# log.net
KiCad netlist of a schematic drawn in EAGLE
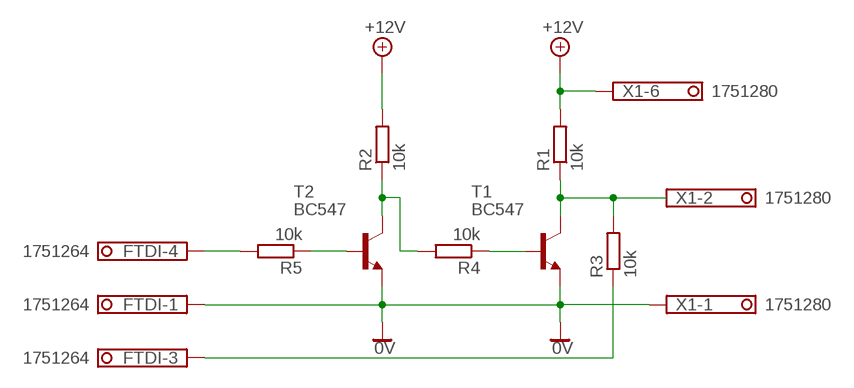
[diagram p0: schematic, sheet 1]

(export (version "E")
  (design (tool "Eeschema 10.0.6"))
  (components
    (comp (ref "FTDI")
      (value "1751264")
      (footprint "eagle-import:1751264")
      (libsource (lib "eagle-import") (part "1751264"))
    )
    (comp (ref "R1")
      (value "10k")
      (footprint "eagle-import:0204_5")
      (libsource (lib "eagle-import") (part "R-EU_0204/5"))
    )
    (comp (ref "R2")
      (value "10k")
      (footprint "eagle-import:0204_5")
      (libsource (lib "eagle-import") (part "R-EU_0204/5"))
    )
    (comp (ref "R3")
      (value "10k")
      (footprint "eagle-import:0204_5")
      (libsource (lib "eagle-import") (part "R-EU_0204/5"))
    )
    (comp (ref "R4")
      (value "10k")
      (footprint "eagle-import:0204_5")
      (libsource (lib "eagle-import") (part "R-EU_0204/5"))
    )
    (comp (ref "R5")
      (value "10k")
      (footprint "eagle-import:0204_5")
      (libsource (lib "eagle-import") (part "R-EU_0204/5"))
    )
    (comp (ref "T1")
      (value "BC547")
      (footprint "eagle-import:TO92")
      (libsource (lib "eagle-import") (part "BC547"))
    )
    (comp (ref "T2")
      (value "BC547")
      (footprint "eagle-import:TO92")
      (libsource (lib "eagle-import") (part "BC547"))
    )
    (comp (ref "X1")
      (value "1751280")
      (footprint "eagle-import:1751280")
      (libsource (lib "eagle-import") (part "1751280"))
    )
  )
  (nets
    (net (code "1") (name "+12V") (class "Default")
      (node (ref "R1") (pin "2") (pinfunction "2_2") (pintype "passive"))
      (node (ref "R2") (pin "2") (pinfunction "2_2") (pintype "passive"))
      (node (ref "X1") (pin "6") (pinfunction "K_6") (pintype "passive"))
    )
    (net (code "2") (name "0V") (class "Default")
      (node (ref "FTDI") (pin "1") (pinfunction "K_1") (pintype "passive"))
      (node (ref "T1") (pin "1") (pinfunction "E_1") (pintype "passive"))
      (node (ref "T2") (pin "1") (pinfunction "E_1") (pintype "passive"))
      (node (ref "X1") (pin "1") (pinfunction "K_1") (pintype "passive"))
    )
    (net (code "3") (name "Net-(FTDIC-K)") (class "Default")
      (node (ref "FTDI") (pin "3") (pinfunction "K_3") (pintype "passive"))
      (node (ref "R3") (pin "1") (pinfunction "1_1") (pintype "passive"))
    )
    (net (code "4") (name "Net-(FTDID-K)") (class "Default")
      (node (ref "FTDI") (pin "4") (pinfunction "K_4") (pintype "passive"))
      (node (ref "R5") (pin "2") (pinfunction "2_2") (pintype "passive"))
    )
    (net (code "5") (name "Net-(T1-B)") (class "Default")
      (node (ref "R4") (pin "1") (pinfunction "1_1") (pintype "passive"))
      (node (ref "T1") (pin "2") (pinfunction "B_2") (pintype "passive"))
    )
    (net (code "6") (name "Net-(T1-C)") (class "Default")
      (node (ref "R1") (pin "1") (pinfunction "1_1") (pintype "passive"))
      (node (ref "R3") (pin "2") (pinfunction "2_2") (pintype "passive"))
      (node (ref "T1") (pin "3") (pinfunction "C_3") (pintype "passive"))
    )
    (net (code "7") (name "Net-(T2-B)") (class "Default")
      (node (ref "R5") (pin "1") (pinfunction "1_1") (pintype "passive"))
      (node (ref "T2") (pin "2") (pinfunction "B_2") (pintype "passive"))
    )
    (net (code "8") (name "Net-(T2-C)") (class "Default")
      (node (ref "R2") (pin "1") (pinfunction "1_1") (pintype "passive"))
      (node (ref "R4") (pin "2") (pinfunction "2_2") (pintype "passive"))
      (node (ref "T2") (pin "3") (pinfunction "C_3") (pintype "passive"))
    )
    (net (code "9") (name "unconnected-(X1B-K-Pad2)") (class "Default")
      (node (ref "X1") (pin "2") (pinfunction "K_2") (pintype "passive"))
    )
  )
)
